# quadcopter.net
KiCad netlist of a schematic drawn in EAGLE
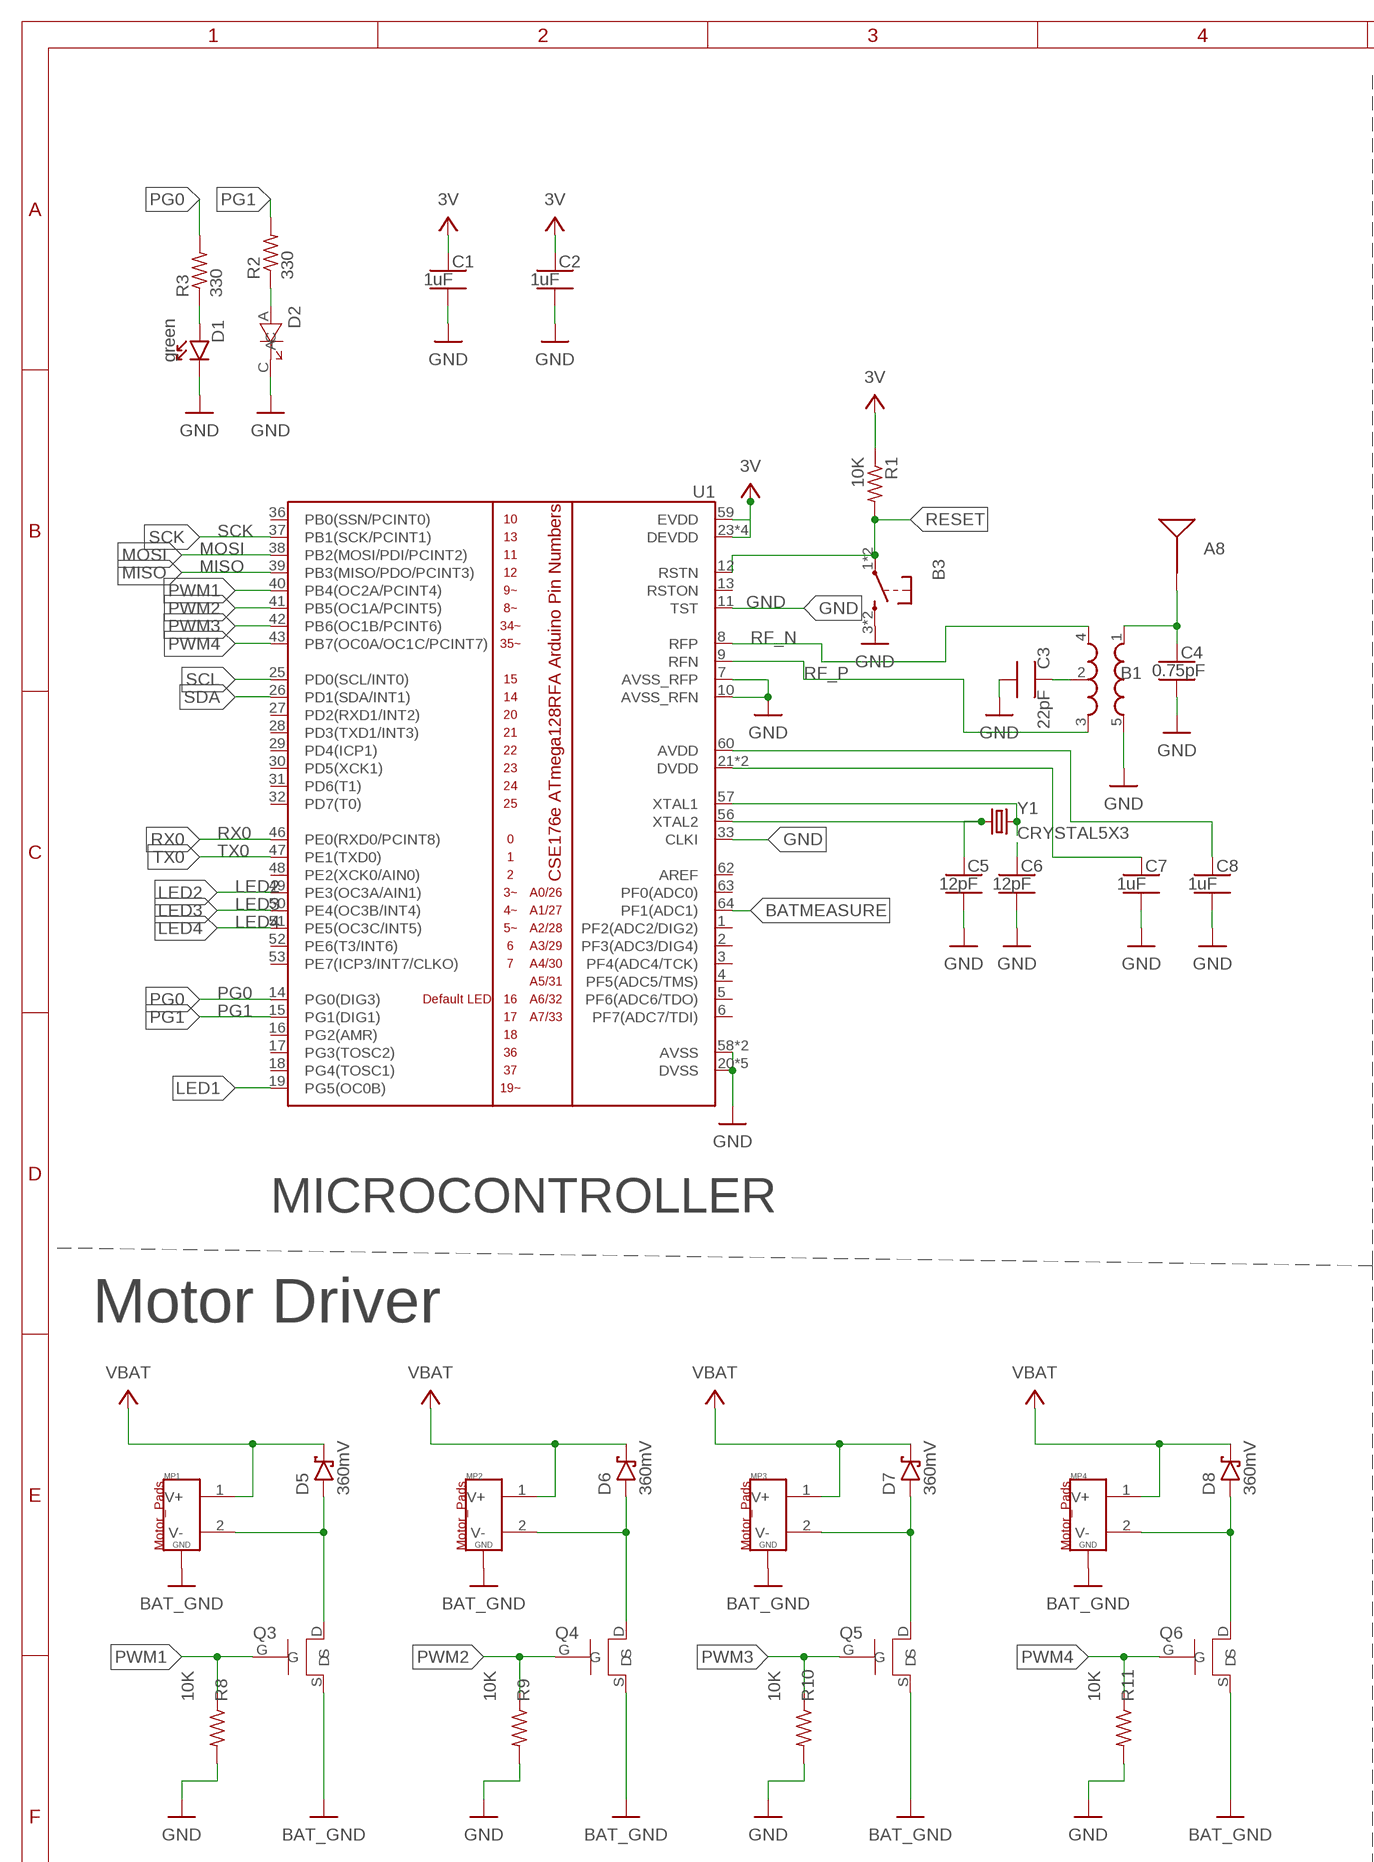
[diagram p0: schematic, sheet 1, part 1 of 2]
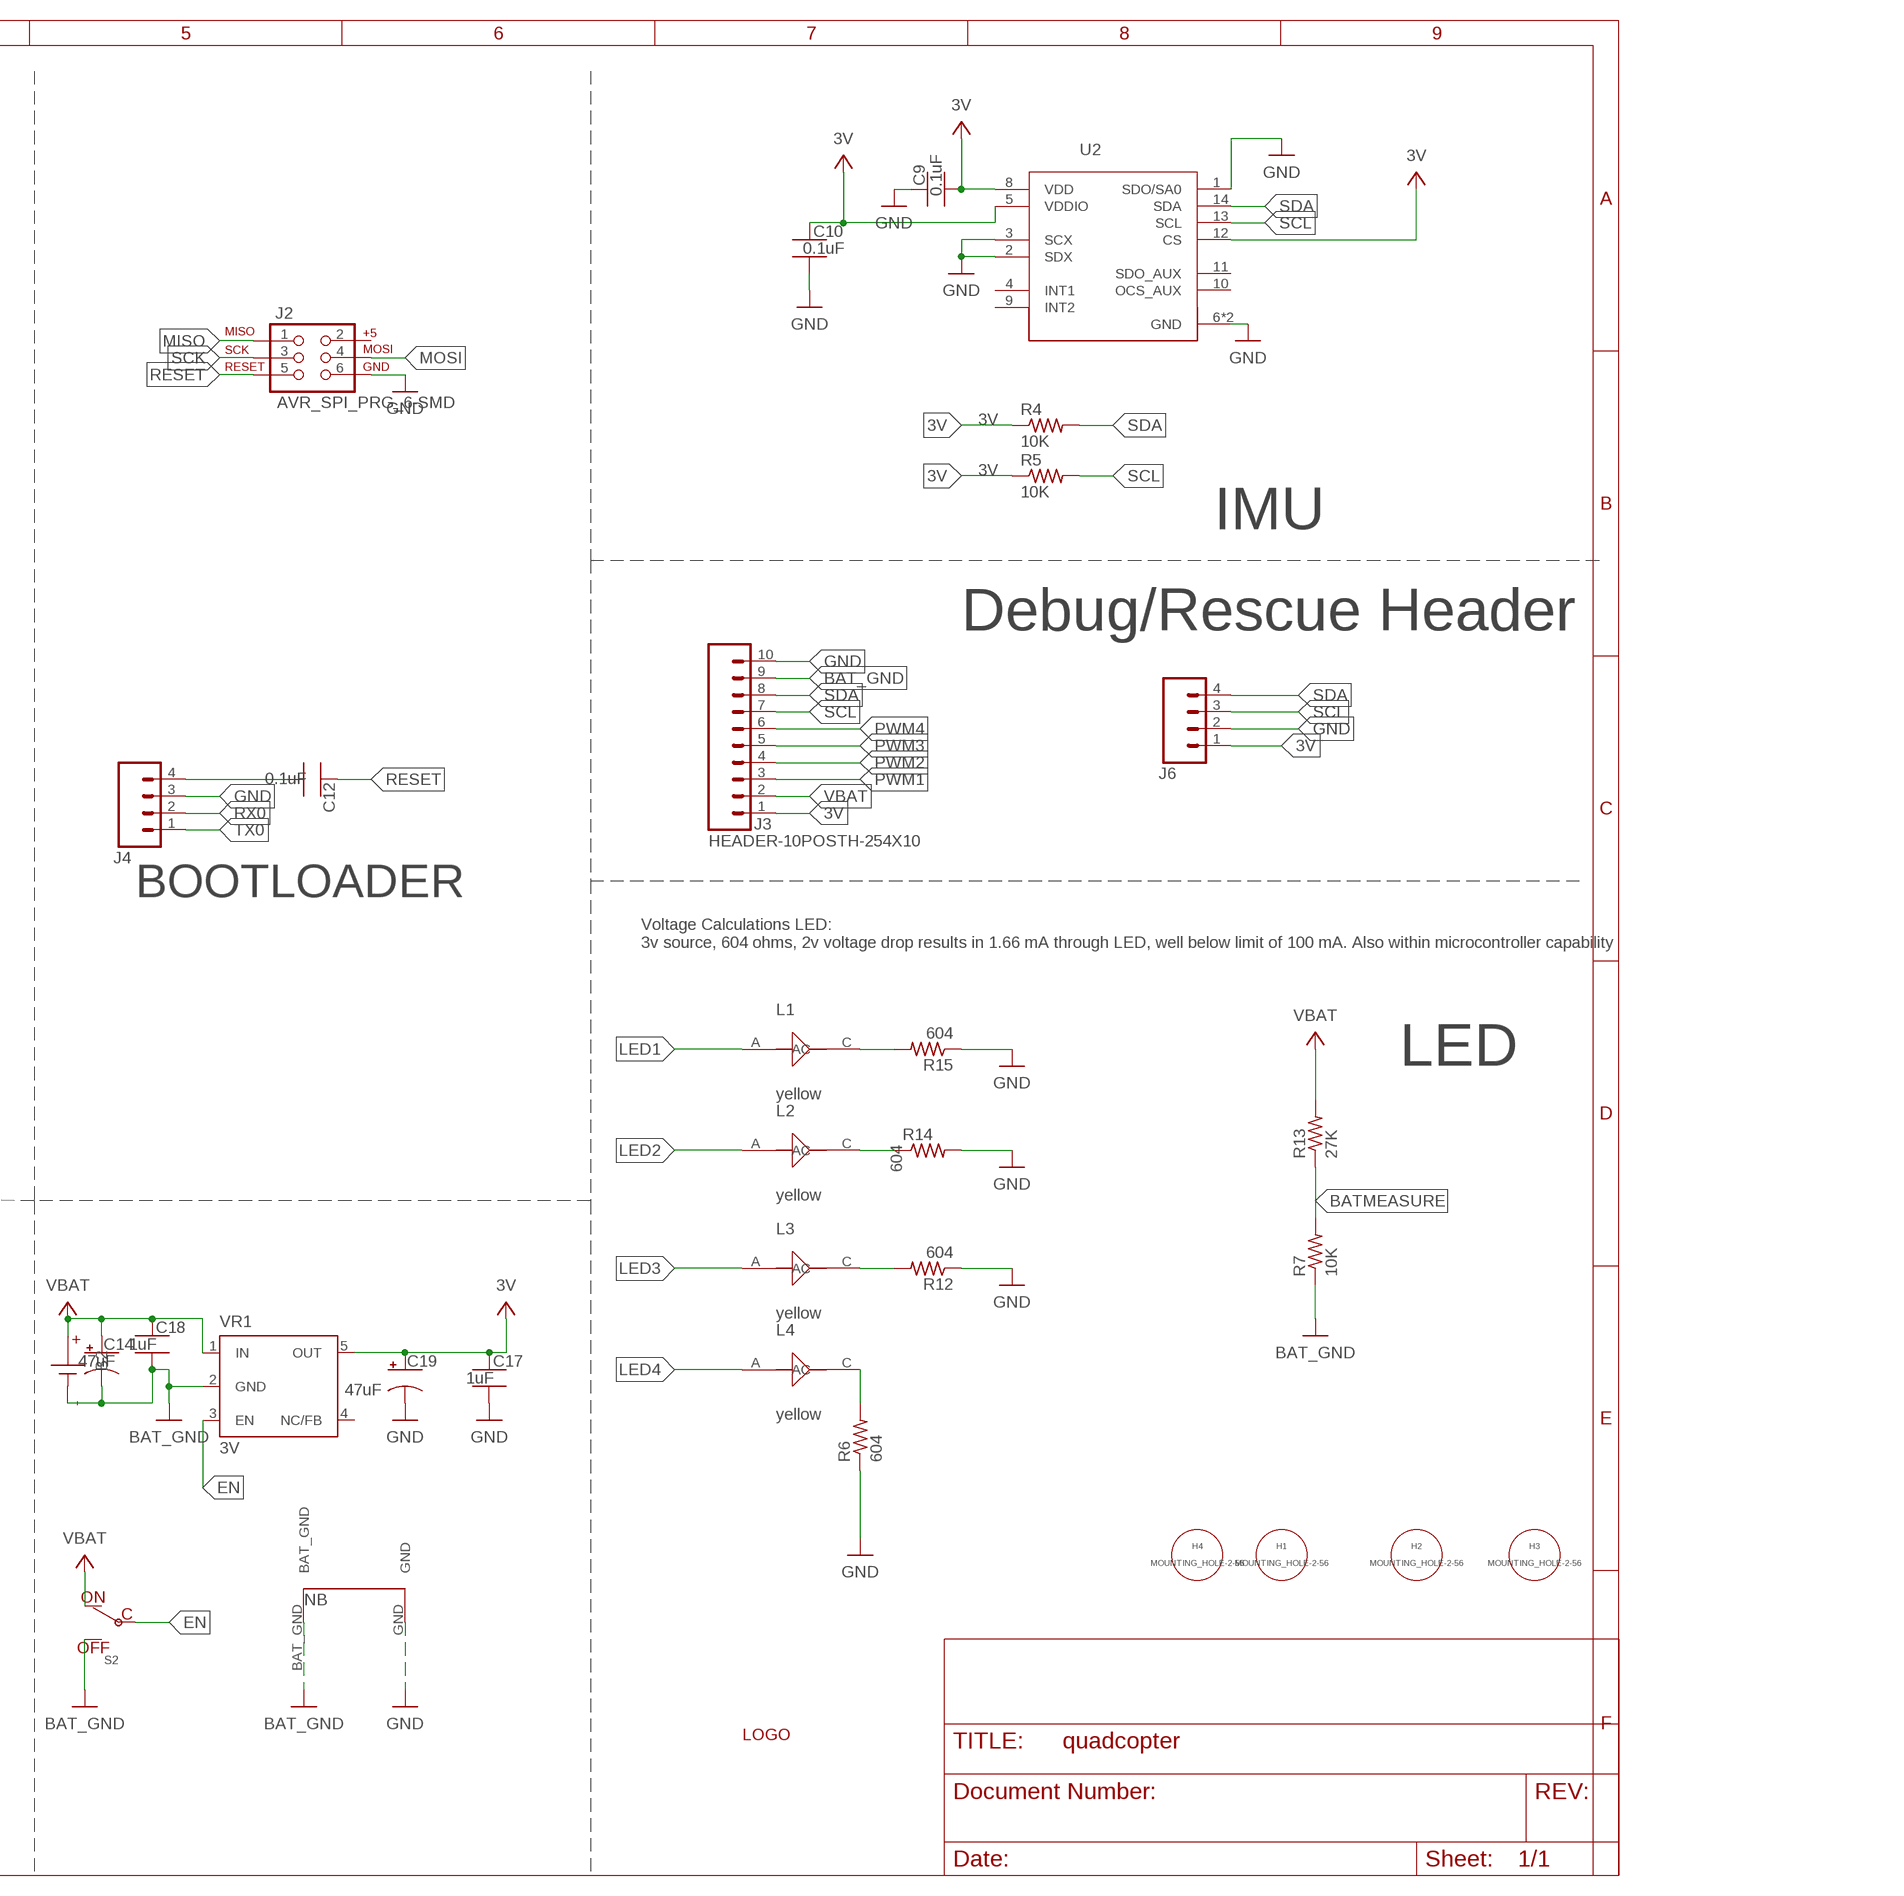
[diagram p1: schematic, sheet 1, part 2 of 2]

(export (version "E")
  (design (tool "Eeschema 10.0.6"))
  (components
    (comp (ref "A8")
      (value "ANTENNA-BOARD")
      (footprint "eagle-import:ANT_PCB_2.4GHZ_NRF8001_1.6MM_1OZ")
      (fields (field (name "MFR") "NA") (field (name "CREATOR") "Swanson"))
      (libsource (lib "eagle-import") (part "ANTENNA-BOARD"))
    )
    (comp (ref "B1")
      (value "BALUN0805")
      (footprint "eagle-import:BALUN")
      (fields
        (field (name "MFR") "Wurth Electronics Inc.")
        (field (name "MPN") "748421245")
        (field (name "CREATOR") "Swanson")
        (field (name "REVIEWER") "Swanson")
      )
      (libsource (lib "eagle-import") (part "BALUN0805"))
    )
    (comp (ref "B2")
      (value "BATTERY-SCREW-TERMINAL")
      (footprint "eagle-import:SCREW-TERMINAL-1X2-2.54MM")
      (fields (field (name "CREATOR") "Swanson"))
      (libsource (lib "eagle-import") (part "BATTERY-SCREW-TERMINAL"))
    )
    (comp (ref "B3")
      (value "PUSHBUTTON_SMD-VERTICAL-1")
      (footprint "eagle-import:TE_FSM8JSMA_HS")
      (fields
        (field (name "MFR") "TE Connectivity Alcoswitch Switches")
        (field (name "MPN") "FSM4JSMA")
        (field (name "CREATOR") "Swanson")
        (field (name "REVIEWER") "Swanson")
      )
      (libsource (lib "eagle-import") (part "PUSHBUTTON_SMD-VERTICAL-1"))
    )
    (comp (ref "C1")
      (value "1uF")
      (footprint "eagle-import:CAPC2012X140_HS")
      (fields
        (field (name "MFR") "Taiyo Yuden")
        (field (name "MPN") "TMK212B7105KG-T")
        (field (name "CREATOR") "Swanson")
        (field (name "REVIEWER") "Swanson")
      )
      (libsource (lib "eagle-import") (part "CAPACITOR-NP_SMD-2012-0805_CERAMIC-1UF"))
    )
    (comp (ref "C2")
      (value "1uF")
      (footprint "eagle-import:CAPC2012X140_HS")
      (fields
        (field (name "MFR") "Taiyo Yuden")
        (field (name "MPN") "TMK212B7105KG-T")
        (field (name "CREATOR") "Swanson")
        (field (name "REVIEWER") "Swanson")
      )
      (libsource (lib "eagle-import") (part "CAPACITOR-NP_SMD-2012-0805_CERAMIC-1UF"))
    )
    (comp (ref "C3")
      (value "22pF")
      (footprint "eagle-import:CAPC2012X140_HS")
      (fields
        (field (name "MFR") "Murata Electronics")
        (field (name "MPN") "GRM21A5C2E220JW01D")
        (field (name "CREATOR") "Swanson")
        (field (name "REVIEWER") "Swanson")
      )
      (libsource (lib "eagle-import") (part "CAPACITOR-NP_SMD-2012-0805_CERAMIC-22PF"))
    )
    (comp (ref "C4")
      (value "0.75pF")
      (footprint "eagle-import:CAPC2012X140_HS")
      (fields
        (field (name "MFR") "Murata Electronics")
        (field (name "MPN") "GQM2195C2AR75CB01D")
        (field (name "CREATOR") "Swanson")
        (field (name "REVIEWER") "Swanson")
      )
      (libsource (lib "eagle-import") (part "CAPACITOR-NP_SMD-2012-0805_CERAMIC-0.75PF"))
    )
    (comp (ref "C5")
      (value "12pF")
      (footprint "eagle-import:CAPC2012X140_HS")
      (fields
        (field (name "MFR") "Murata Electronics")
        (field (name "MPN") "GRM21A5C2E120JW01D")
        (field (name "CREATOR") "Swanson")
        (field (name "REVIEWER") "Swanson")
      )
      (libsource (lib "eagle-import") (part "CAPACITOR-NP_SMD-2012-0805_CERAMIC-12PF"))
    )
    (comp (ref "C6")
      (value "12pF")
      (footprint "eagle-import:CAPC2012X140_HS")
      (fields
        (field (name "MFR") "Murata Electronics")
        (field (name "MPN") "GRM21A5C2E120JW01D")
        (field (name "CREATOR") "Swanson")
        (field (name "REVIEWER") "Swanson")
      )
      (libsource (lib "eagle-import") (part "CAPACITOR-NP_SMD-2012-0805_CERAMIC-12PF"))
    )
    (comp (ref "C7")
      (value "1uF")
      (footprint "eagle-import:CAPC2012X140_HS")
      (fields
        (field (name "MFR") "Taiyo Yuden")
        (field (name "MPN") "TMK212B7105KG-T")
        (field (name "CREATOR") "Swanson")
        (field (name "REVIEWER") "Swanson")
      )
      (libsource (lib "eagle-import") (part "CAPACITOR-NP_SMD-2012-0805_CERAMIC-1UF"))
    )
    (comp (ref "C8")
      (value "1uF")
      (footprint "eagle-import:CAPC2012X140_HS")
      (fields
        (field (name "MFR") "Taiyo Yuden")
        (field (name "MPN") "TMK212B7105KG-T")
        (field (name "CREATOR") "Swanson")
        (field (name "REVIEWER") "Swanson")
      )
      (libsource (lib "eagle-import") (part "CAPACITOR-NP_SMD-2012-0805_CERAMIC-1UF"))
    )
    (comp (ref "C9")
      (value "0.1uF")
      (footprint "eagle-import:CAPC2012X140_HS")
      (fields
        (field (name "MFR") "TDK Corporation")
        (field (name "MPN") "C2012X7R2A104K125AA")
        (field (name "CREATOR") "Swanson")
        (field (name "REVIEWER") "Swanson")
      )
      (libsource (lib "eagle-import") (part "CAPACITOR-NP_SMD-2012-0805_CERAMIC-0.1UF"))
    )
    (comp (ref "C10")
      (value "0.1uF")
      (footprint "eagle-import:CAPC2012X140_HS")
      (fields
        (field (name "MFR") "TDK Corporation")
        (field (name "MPN") "C2012X7R2A104K125AA")
        (field (name "CREATOR") "Swanson")
        (field (name "REVIEWER") "Swanson")
      )
      (libsource (lib "eagle-import") (part "CAPACITOR-NP_SMD-2012-0805_CERAMIC-0.1UF"))
    )
    (comp (ref "C12")
      (value "0.1uF")
      (footprint "eagle-import:CAPC2012X140_HS")
      (fields
        (field (name "MFR") "TDK Corporation")
        (field (name "MPN") "C2012X7R2A104K125AA")
        (field (name "CREATOR") "Swanson")
        (field (name "REVIEWER") "Swanson")
      )
      (libsource (lib "eagle-import") (part "CAPACITOR-NP_SMD-2012-0805_CERAMIC-0.1UF"))
    )
    (comp (ref "C14")
      (value "47uF")
      (footprint "eagle-import:CAPMP3216X180")
      (fields
        (field (name "MFR") "AVX Corporation")
        (field (name "MPN") "TAJA476K006SNJV")
        (field (name "CREATOR") "Swanson")
      )
      (libsource (lib "eagle-import") (part "CAPACITOR-POL_47UF-SMD-1206-TAJA"))
    )
    (comp (ref "C17")
      (value "1uF")
      (footprint "eagle-import:CAPC2012X140_HS")
      (fields
        (field (name "MFR") "Taiyo Yuden")
        (field (name "MPN") "TMK212B7105KG-T")
        (field (name "CREATOR") "Swanson")
        (field (name "REVIEWER") "Swanson")
      )
      (libsource (lib "eagle-import") (part "CAPACITOR-NP_SMD-2012-0805_CERAMIC-1UF"))
    )
    (comp (ref "C18")
      (value "1uF")
      (footprint "eagle-import:CAPC2012X140_HS")
      (fields
        (field (name "MFR") "Taiyo Yuden")
        (field (name "MPN") "TMK212B7105KG-T")
        (field (name "CREATOR") "Swanson")
        (field (name "REVIEWER") "Swanson")
      )
      (libsource (lib "eagle-import") (part "CAPACITOR-NP_SMD-2012-0805_CERAMIC-1UF"))
    )
    (comp (ref "C19")
      (value "47uF")
      (footprint "eagle-import:CAPMP3216X180")
      (fields
        (field (name "MFR") "AVX Corporation")
        (field (name "MPN") "TAJA476K006SNJV")
        (field (name "CREATOR") "Swanson")
      )
      (libsource (lib "eagle-import") (part "CAPACITOR-POL_47UF-SMD-1206-TAJA"))
    )
    (comp (ref "D1")
      (value "green")
      (footprint "eagle-import:LEDSC125X200X120-2_HS")
      (fields
        (field (name "MFR") "Lite-On Inc")
        (field (name "MPN") "LTST-C170GKT")
        (field (name "CREATOR") "Swanson")
        (field (name "REVIEWER") "Swanson")
      )
      (libsource (lib "eagle-import") (part "DIODE-LED_SMD-2012-0805-GREEN"))
    )
    (comp (ref "D2")
      (value "LED-RED-160-1178-1-ND")
      (footprint "eagle-import:LED_160-1178-1-ND")
      (fields (field (name "CREATOR") "KaustubhKanagalekar"))
      (libsource (lib "eagle-import") (part "LED-RED-160-1178-1-ND"))
    )
    (comp (ref "D5")
      (value "360mV")
      (footprint "eagle-import:SODFL3516X96")
      (fields
        (field (name "MFR") "Toshiba Semiconductor and Storage")
        (field (name "MPN") "CRS08(TE85L,Q,M)")
        (field (name "CREATOR") "Swanson")
        (field (name "REVIEWER") "Swanson")
      )
      (libsource (lib "eagle-import") (part "DIODE-SCHOTTKY_-SMD-SOD123"))
    )
    (comp (ref "D6")
      (value "360mV")
      (footprint "eagle-import:SODFL3516X96")
      (fields
        (field (name "MFR") "Toshiba Semiconductor and Storage")
        (field (name "MPN") "CRS08(TE85L,Q,M)")
        (field (name "CREATOR") "Swanson")
        (field (name "REVIEWER") "Swanson")
      )
      (libsource (lib "eagle-import") (part "DIODE-SCHOTTKY_-SMD-SOD123"))
    )
    (comp (ref "D7")
      (value "360mV")
      (footprint "eagle-import:SODFL3516X96")
      (fields
        (field (name "MFR") "Toshiba Semiconductor and Storage")
        (field (name "MPN") "CRS08(TE85L,Q,M)")
        (field (name "CREATOR") "Swanson")
        (field (name "REVIEWER") "Swanson")
      )
      (libsource (lib "eagle-import") (part "DIODE-SCHOTTKY_-SMD-SOD123"))
    )
    (comp (ref "D8")
      (value "360mV")
      (footprint "eagle-import:SODFL3516X96")
      (fields
        (field (name "MFR") "Toshiba Semiconductor and Storage")
        (field (name "MPN") "CRS08(TE85L,Q,M)")
        (field (name "CREATOR") "Swanson")
        (field (name "REVIEWER") "Swanson")
      )
      (libsource (lib "eagle-import") (part "DIODE-SCHOTTKY_-SMD-SOD123"))
    )
    (comp (ref "H1")
      (value "MOUNTING_HOLE-2-56")
      (footprint "eagle-import:2-56-MOUNTING-HOLE-NO-METAL")
      (libsource (lib "eagle-import") (part "MOUNTING_HOLE-2-56"))
    )
    (comp (ref "H2")
      (value "MOUNTING_HOLE-2-56")
      (footprint "eagle-import:2-56-MOUNTING-HOLE-NO-METAL")
      (libsource (lib "eagle-import") (part "MOUNTING_HOLE-2-56"))
    )
    (comp (ref "H3")
      (value "MOUNTING_HOLE-2-56")
      (footprint "eagle-import:2-56-MOUNTING-HOLE-NO-METAL")
      (libsource (lib "eagle-import") (part "MOUNTING_HOLE-2-56"))
    )
    (comp (ref "H4")
      (value "MOUNTING_HOLE-2-56")
      (footprint "eagle-import:2-56-MOUNTING-HOLE-NO-METAL")
      (libsource (lib "eagle-import") (part "MOUNTING_HOLE-2-56"))
    )
    (comp (ref "J2")
      (value "AVR_SPI_PRG_6-SMD")
      (footprint "eagle-import:2X3-SMD")
      (fields
        (field (name "MFR") "Amphenol ICC (FCI)")
        (field (name "MPN") "95278-101A06LF")
        (field (name "CREATOR") "Swanson")
      )
      (libsource (lib "eagle-import") (part "AVR_SPI_PRG_6-SMD"))
    )
    (comp (ref "J3")
      (value "HEADER-10POSTH-254X10")
      (footprint "eagle-import:HDRV10W63P254_10X1_2540X254H838_HS")
      (fields
        (field (name "MFR") "Amphenol FCI")
        (field (name "MPN") "68000-110HLF")
        (field (name "CREATOR") "Swanson")
        (field (name "REVIEWER") "Swanson")
      )
      (libsource (lib "eagle-import") (part "HEADER-10POSTH-254X10"))
    )
    (comp (ref "J4")
      (value "HEADER-4POS-0.1IN-FEMALE-SMD-BOTTOM-ENTRY")
      (footprint "eagle-import:HEADER-1X4-BOTTOM-ENTRY")
      (fields
        (field (name "MFR") "TE Connectivity AMP Connectors")
        (field (name "MPN") "1241152-4")
        (field (name "CREATOR") "Swanson")
      )
      (libsource (lib "eagle-import") (part "HEADER-4POS-0.1IN-FEMALE-SMD-BOTTOM-ENTRY"))
    )
    (comp (ref "J6")
      (value "HEADER-4POS-0.1IN-FEMALE")
      (footprint "eagle-import:HDRVR4W80P254_1X4_1066X254X850B")
      (fields (field (name "CREATOR") "Swanson"))
      (libsource (lib "eagle-import") (part "HEADER-4POS-0.1IN-FEMALE"))
    )
    (comp (ref "L1")
      (value "yellow")
      (footprint "eagle-import:LEDC1507X80NYELLOW")
      (fields (field (name "CREATOR") "AlexanderHaken"))
      (libsource (lib "eagle-import") (part "LED_YELLOW"))
    )
    (comp (ref "L2")
      (value "yellow")
      (footprint "eagle-import:LEDC1507X80NYELLOW")
      (fields (field (name "CREATOR") "AlexanderHaken"))
      (libsource (lib "eagle-import") (part "LED_YELLOW"))
    )
    (comp (ref "L3")
      (value "yellow")
      (footprint "eagle-import:LEDC1507X80NYELLOW")
      (fields (field (name "CREATOR") "AlexanderHaken"))
      (libsource (lib "eagle-import") (part "LED_YELLOW"))
    )
    (comp (ref "L4")
      (value "yellow")
      (footprint "eagle-import:LEDC1507X80NYELLOW")
      (fields (field (name "CREATOR") "AlexanderHaken"))
      (libsource (lib "eagle-import") (part "LED_YELLOW"))
    )
    (comp (ref "LOGO")
      (value "PIDLOGO")
      (footprint "eagle-import:PIDLOGO")
      (libsource (lib "eagle-import") (part "PIDLOGO"))
    )
    (comp (ref "MP1")
      (value "MOTOR_PADS_GND-MOLEX-SMD")
      (footprint "eagle-import:MOLEX-0532610271")
      (fields
        (field (name "MFR") "Molex")
        (field (name "MPN") "532610271")
        (field (name "CREATOR") "Swanson")
      )
      (libsource (lib "eagle-import") (part "MOTOR_PADS_GND-MOLEX-SMD"))
    )
    (comp (ref "MP2")
      (value "MOTOR_PADS_GND-MOLEX-SMD")
      (footprint "eagle-import:MOLEX-0532610271")
      (fields
        (field (name "MFR") "Molex")
        (field (name "MPN") "532610271")
        (field (name "CREATOR") "Swanson")
      )
      (libsource (lib "eagle-import") (part "MOTOR_PADS_GND-MOLEX-SMD"))
    )
    (comp (ref "MP3")
      (value "MOTOR_PADS_GND-MOLEX-SMD")
      (footprint "eagle-import:MOLEX-0532610271")
      (fields
        (field (name "MFR") "Molex")
        (field (name "MPN") "532610271")
        (field (name "CREATOR") "Swanson")
      )
      (libsource (lib "eagle-import") (part "MOTOR_PADS_GND-MOLEX-SMD"))
    )
    (comp (ref "MP4")
      (value "MOTOR_PADS_GND-MOLEX-SMD")
      (footprint "eagle-import:MOLEX-0532610271")
      (fields
        (field (name "MFR") "Molex")
        (field (name "MPN") "532610271")
        (field (name "CREATOR") "Swanson")
      )
      (libsource (lib "eagle-import") (part "MOTOR_PADS_GND-MOLEX-SMD"))
    )
    (comp (ref "NB")
      (value "NETBRIDGE")
      (footprint "eagle-import:NETBRIDGE")
      (libsource (lib "eagle-import") (part "NETBRIDGE"))
    )
    (comp (ref "Q3")
      (value "MOSFET-FET-SI2302CDS-T1-E3CT-NDSI2302CDS-T1-E3CT-ND")
      (footprint "eagle-import:MOSFET_FET_SI2302CDS-T1-E3CT-ND")
      (fields (field (name "CREATOR") "KaustubhKanagalekar"))
      (libsource (lib "eagle-import") (part "MOSFET-FET-SI2302CDS-T1-E3CT-NDSI2302CDS-T1-E3CT-ND"))
    )
    (comp (ref "Q4")
      (value "MOSFET-FET-SI2302CDS-T1-E3CT-NDSI2302CDS-T1-E3CT-ND")
      (footprint "eagle-import:MOSFET_FET_SI2302CDS-T1-E3CT-ND")
      (fields (field (name "CREATOR") "KaustubhKanagalekar"))
      (libsource (lib "eagle-import") (part "MOSFET-FET-SI2302CDS-T1-E3CT-NDSI2302CDS-T1-E3CT-ND"))
    )
    (comp (ref "Q5")
      (value "MOSFET-FET-SI2302CDS-T1-E3CT-NDSI2302CDS-T1-E3CT-ND")
      (footprint "eagle-import:MOSFET_FET_SI2302CDS-T1-E3CT-ND")
      (fields (field (name "CREATOR") "KaustubhKanagalekar"))
      (libsource (lib "eagle-import") (part "MOSFET-FET-SI2302CDS-T1-E3CT-NDSI2302CDS-T1-E3CT-ND"))
    )
    (comp (ref "Q6")
      (value "MOSFET-FET-SI2302CDS-T1-E3CT-NDSI2302CDS-T1-E3CT-ND")
      (footprint "eagle-import:MOSFET_FET_SI2302CDS-T1-E3CT-ND")
      (fields (field (name "CREATOR") "KaustubhKanagalekar"))
      (libsource (lib "eagle-import") (part "MOSFET-FET-SI2302CDS-T1-E3CT-NDSI2302CDS-T1-E3CT-ND"))
    )
    (comp (ref "R1")
      (value "10K")
      (footprint "eagle-import:RESC2012X60_HS")
      (fields
        (field (name "MFR") "Yageo")
        (field (name "MPN") "RC0805JR-0710KL")
        (field (name "CREATOR") "Swanson")
        (field (name "REVIEWER") "Swanson")
      )
      (libsource (lib "eagle-import") (part "RESISTOR_SMD-2012-0805-10K"))
    )
    (comp (ref "R2")
      (value "330")
      (footprint "eagle-import:RESC2012X60_HS")
      (fields
        (field (name "MFR") "Yageo")
        (field (name "MPN") "RC0805JR-07330RL")
        (field (name "CREATOR") "Swanson")
        (field (name "REVIEWER") "Swanson")
      )
      (libsource (lib "eagle-import") (part "RESISTOR_SMD-2012-0805-330"))
    )
    (comp (ref "R3")
      (value "330")
      (footprint "eagle-import:RESC2012X60_HS")
      (fields
        (field (name "MFR") "Yageo")
        (field (name "MPN") "RC0805JR-07330RL")
        (field (name "CREATOR") "Swanson")
        (field (name "REVIEWER") "Swanson")
      )
      (libsource (lib "eagle-import") (part "RESISTOR_SMD-2012-0805-330"))
    )
    (comp (ref "R4")
      (value "10K")
      (footprint "eagle-import:RESC2012X60_HS")
      (fields
        (field (name "MFR") "Yageo")
        (field (name "MPN") "RC0805JR-0710KL")
        (field (name "CREATOR") "Swanson")
        (field (name "REVIEWER") "Swanson")
      )
      (libsource (lib "eagle-import") (part "RESISTOR_SMD-2012-0805-10K"))
    )
    (comp (ref "R5")
      (value "10K")
      (footprint "eagle-import:RESC2012X60_HS")
      (fields
        (field (name "MFR") "Yageo")
        (field (name "MPN") "RC0805JR-0710KL")
        (field (name "CREATOR") "Swanson")
        (field (name "REVIEWER") "Swanson")
      )
      (libsource (lib "eagle-import") (part "RESISTOR_SMD-2012-0805-10K"))
    )
    (comp (ref "R6")
      (value "604")
      (footprint "eagle-import:RESC2012X60_HS")
      (fields (field (name "CREATOR") "Swanson"))
      (libsource (lib "eagle-import") (part "RESISTOR_SMD-2012-0805-604"))
    )
    (comp (ref "R7")
      (value "10K")
      (footprint "eagle-import:RESC2012X60_HS")
      (fields
        (field (name "MFR") "Yageo")
        (field (name "MPN") "RC0805JR-0710KL")
        (field (name "CREATOR") "Swanson")
        (field (name "REVIEWER") "Swanson")
      )
      (libsource (lib "eagle-import") (part "RESISTOR_SMD-2012-0805-10K"))
    )
    (comp (ref "R8")
      (value "10K")
      (footprint "eagle-import:RESC2012X60_HS")
      (fields
        (field (name "MFR") "Yageo")
        (field (name "MPN") "RC0805JR-0710KL")
        (field (name "CREATOR") "Swanson")
        (field (name "REVIEWER") "Swanson")
      )
      (libsource (lib "eagle-import") (part "RESISTOR_SMD-2012-0805-10K"))
    )
    (comp (ref "R9")
      (value "10K")
      (footprint "eagle-import:RESC2012X60_HS")
      (fields
        (field (name "MFR") "Yageo")
        (field (name "MPN") "RC0805JR-0710KL")
        (field (name "CREATOR") "Swanson")
        (field (name "REVIEWER") "Swanson")
      )
      (libsource (lib "eagle-import") (part "RESISTOR_SMD-2012-0805-10K"))
    )
    (comp (ref "R10")
      (value "10K")
      (footprint "eagle-import:RESC2012X60_HS")
      (fields
        (field (name "MFR") "Yageo")
        (field (name "MPN") "RC0805JR-0710KL")
        (field (name "CREATOR") "Swanson")
        (field (name "REVIEWER") "Swanson")
      )
      (libsource (lib "eagle-import") (part "RESISTOR_SMD-2012-0805-10K"))
    )
    (comp (ref "R11")
      (value "10K")
      (footprint "eagle-import:RESC2012X60_HS")
      (fields
        (field (name "MFR") "Yageo")
        (field (name "MPN") "RC0805JR-0710KL")
        (field (name "CREATOR") "Swanson")
        (field (name "REVIEWER") "Swanson")
      )
      (libsource (lib "eagle-import") (part "RESISTOR_SMD-2012-0805-10K"))
    )
    (comp (ref "R12")
      (value "604")
      (footprint "eagle-import:RESC2012X60_HS")
      (fields (field (name "CREATOR") "Swanson"))
      (libsource (lib "eagle-import") (part "RESISTOR_SMD-2012-0805-604"))
    )
    (comp (ref "R13")
      (value "27K")
      (footprint "eagle-import:RESC2012X60_HS")
      (fields (field (name "CREATOR") "Swanson"))
      (libsource (lib "eagle-import") (part "RESISTOR_SMD-2012-0805-27K"))
    )
    (comp (ref "R14")
      (value "604")
      (footprint "eagle-import:RESC2012X60_HS")
      (fields (field (name "CREATOR") "Swanson"))
      (libsource (lib "eagle-import") (part "RESISTOR_SMD-2012-0805-604"))
    )
    (comp (ref "R15")
      (value "604")
      (footprint "eagle-import:RESC2012X60_HS")
      (fields (field (name "CREATOR") "Swanson"))
      (libsource (lib "eagle-import") (part "RESISTOR_SMD-2012-0805-604"))
    )
    (comp (ref "S2")
      (value "POWER-SWITCH-MFS201N-9-Z-SMD-EDGE")
      (footprint "eagle-import:JS102011SAQN")
      (fields
        (field (name "MFR") "C&K")
        (field (name "MPN") "JS102011SAQN")
        (field (name "CREATOR") "Swanson")
      )
      (libsource (lib "eagle-import") (part "POWER-SWITCH-MFS201N-9-Z-SMD-EDGE"))
    )
    (comp (ref "U1")
      (value "ATMEGA128RFA1")
      (footprint "eagle-import:QFN-64")
      (fields
        (field (name "MFR") "Microchip Technology")
        (field (name "MPN") "ATMEGA128RFA1-ZU")
        (field (name "CREATOR") "Swanson")
        (field (name "REVIEWER") "Swanson")
      )
      (libsource (lib "eagle-import") (part "ATMEGA128RFA1"))
    )
    (comp (ref "U2")
      (value "IMU-LSM6DSOXTR-497-18367-1-ND497-18367-1-ND")
      (footprint "eagle-import:LSM6DS0")
      (fields (field (name "CREATOR") "KaustubhKanagalekar"))
      (libsource (lib "eagle-import") (part "IMU-LSM6DSOXTR-497-18367-1-ND497-18367-1-ND"))
    )
    (comp (ref "VR1")
      (value "3V")
      (footprint "eagle-import:SOT23-DBV")
      (fields
        (field (name "MFR") "Texas Instruments")
        (field (name "MPN") "LP3985IM5X-3.0/NOPB")
        (field (name "CREATOR") "Swanson")
        (field (name "REVIEWER") "Swanson")
      )
      (libsource (lib "eagle-import") (part "TPS73633-DBVT3V"))
    )
    (comp (ref "Y1")
      (value "CRYSTAL5X3")
      (footprint "eagle-import:CRYSTAL-SMD-5X3")
      (fields
        (field (name "MFR") "Abracon LLC")
        (field (name "MPN") "ABM3B-16.000MHZ-B2-T")
        (field (name "CREATOR") "Swanson")
        (field (name "REVIEWER") "Swanson")
      )
      (libsource (lib "eagle-import") (part "CRYSTAL5X3"))
    )
  )
  (nets
    (net (code "1") (name "/RF_N") (class "Default")
      (node (ref "B1") (pin "4") (pinfunction "OUT1_4") (pintype "bidirectional"))
      (node (ref "U1") (pin "8") (pinfunction "RFP_8") (pintype "bidirectional"))
    )
    (net (code "2") (name "/RF_P") (class "Default")
      (node (ref "B1") (pin "3") (pinfunction "OUT2_3") (pintype "bidirectional"))
      (node (ref "U1") (pin "9") (pinfunction "RFN_9") (pintype "bidirectional"))
    )
    (net (code "3") (name "3V") (class "Default")
      (node (ref "C1") (pin "1") (pinfunction "1_1") (pintype "passive"))
      (node (ref "C10") (pin "1") (pinfunction "1_1") (pintype "passive"))
      (node (ref "C17") (pin "1") (pinfunction "1_1") (pintype "passive"))
      (node (ref "C19") (pin "1") (pinfunction "+_1") (pintype "passive"))
      (node (ref "C2") (pin "1") (pinfunction "1_1") (pintype "passive"))
      (node (ref "C9") (pin "2") (pinfunction "2_2") (pintype "passive"))
      (node (ref "J3") (pin "1") (pinfunction "1_1") (pintype "passive"))
      (node (ref "J6") (pin "1") (pinfunction "1_1") (pintype "bidirectional"))
      (node (ref "R1") (pin "1") (pinfunction "1_1") (pintype "passive"))
      (node (ref "R4") (pin "1") (pinfunction "1_1") (pintype "passive"))
      (node (ref "R5") (pin "1") (pinfunction "1_1") (pintype "passive"))
      (node (ref "U1") (pin "23") (pinfunction "DEVDD_23") (pintype "bidirectional"))
      (node (ref "U1") (pin "34") (pinfunction "DEVDD_34") (pintype "bidirectional"))
      (node (ref "U1") (pin "44") (pinfunction "DEVDD_44") (pintype "bidirectional"))
      (node (ref "U1") (pin "54") (pinfunction "DEVDD_54") (pintype "bidirectional"))
      (node (ref "U1") (pin "59") (pinfunction "EVDD_59") (pintype "bidirectional"))
      (node (ref "U2") (pin "12") (pinfunction "CS_12") (pintype "bidirectional"))
      (node (ref "U2") (pin "5") (pinfunction "VDDIO_5") (pintype "bidirectional"))
      (node (ref "U2") (pin "8") (pinfunction "VDD_8") (pintype "bidirectional"))
      (node (ref "VR1") (pin "5") (pinfunction "OUT_5") (pintype "passive"))
    )
    (net (code "4") (name "BATMEASURE") (class "Default")
      (node (ref "R13") (pin "1") (pinfunction "1_1") (pintype "passive"))
      (node (ref "R7") (pin "2") (pinfunction "2_2") (pintype "passive"))
      (node (ref "U1") (pin "64") (pinfunction "PF1(ADC1)_64") (pintype "bidirectional"))
    )
    (net (code "5") (name "BAT_GND") (class "Default")
      (node (ref "B2") (pin "1") (pinfunction "N_1") (pintype "bidirectional"))
      (node (ref "C14") (pin "2") (pinfunction "-_2") (pintype "passive"))
      (node (ref "C18") (pin "2") (pinfunction "2_2") (pintype "passive"))
      (node (ref "J3") (pin "9") (pinfunction "9_9") (pintype "passive"))
      (node (ref "MP1") (pin "G1") (pinfunction "GND_G1") (pintype "bidirectional"))
      (node (ref "MP1") (pin "G2") (pinfunction "GND_G2") (pintype "bidirectional"))
      (node (ref "MP2") (pin "G1") (pinfunction "GND_G1") (pintype "bidirectional"))
      (node (ref "MP2") (pin "G2") (pinfunction "GND_G2") (pintype "bidirectional"))
      (node (ref "MP3") (pin "G1") (pinfunction "GND_G1") (pintype "bidirectional"))
      (node (ref "MP3") (pin "G2") (pinfunction "GND_G2") (pintype "bidirectional"))
      (node (ref "MP4") (pin "G1") (pinfunction "GND_G1") (pintype "bidirectional"))
      (node (ref "MP4") (pin "G2") (pinfunction "GND_G2") (pintype "bidirectional"))
      (node (ref "NB") (pin "BAT_GND") (pinfunction "BAT_GND_BAT_GND") (pintype "bidirectional"))
      (node (ref "Q3") (pin "S") (pinfunction "S_S") (pintype "bidirectional"))
      (node (ref "Q4") (pin "S") (pinfunction "S_S") (pintype "bidirectional"))
      (node (ref "Q5") (pin "S") (pinfunction "S_S") (pintype "bidirectional"))
      (node (ref "Q6") (pin "S") (pinfunction "S_S") (pintype "bidirectional"))
      (node (ref "R7") (pin "1") (pinfunction "1_1") (pintype "passive"))
      (node (ref "S2") (pin "A") (pinfunction "OFF_A") (pintype "bidirectional"))
      (node (ref "VR1") (pin "2") (pinfunction "GND_2") (pintype "input"))
    )
    (net (code "6") (name "EN") (class "Default")
      (node (ref "S2") (pin "C") (pinfunction "C_C") (pintype "bidirectional"))
      (node (ref "VR1") (pin "3") (pinfunction "EN_3") (pintype "input"))
    )
    (net (code "7") (name "GND") (class "Default")
      (node (ref "B1") (pin "5") (pinfunction "GND_5") (pintype "bidirectional"))
      (node (ref "B3") (pin "3") (pinfunction "2_3") (pintype "passive"))
      (node (ref "B3") (pin "4") (pinfunction "2_4") (pintype "passive"))
      (node (ref "C1") (pin "2") (pinfunction "2_2") (pintype "passive"))
      (node (ref "C10") (pin "2") (pinfunction "2_2") (pintype "passive"))
      (node (ref "C17") (pin "2") (pinfunction "2_2") (pintype "passive"))
      (node (ref "C19") (pin "2") (pinfunction "-_2") (pintype "passive"))
      (node (ref "C2") (pin "2") (pinfunction "2_2") (pintype "passive"))
      (node (ref "C3") (pin "2") (pinfunction "2_2") (pintype "passive"))
      (node (ref "C4") (pin "2") (pinfunction "2_2") (pintype "passive"))
      (node (ref "C5") (pin "2") (pinfunction "2_2") (pintype "passive"))
      (node (ref "C6") (pin "2") (pinfunction "2_2") (pintype "passive"))
      (node (ref "C7") (pin "2") (pinfunction "2_2") (pintype "passive"))
      (node (ref "C8") (pin "2") (pinfunction "2_2") (pintype "passive"))
      (node (ref "C9") (pin "1") (pinfunction "1_1") (pintype "passive"))
      (node (ref "D1") (pin "C") (pinfunction "C_C") (pintype "passive"))
      (node (ref "D2") (pin "C") (pinfunction "C_C") (pintype "bidirectional"))
      (node (ref "J2") (pin "6") (pinfunction "6_6") (pintype "passive"))
      (node (ref "J3") (pin "10") (pinfunction "10_10") (pintype "passive"))
      (node (ref "J4") (pin "3") (pinfunction "3_3") (pintype "bidirectional"))
      (node (ref "J6") (pin "2") (pinfunction "2_2") (pintype "bidirectional"))
      (node (ref "NB") (pin "GND") (pinfunction "GND_GND") (pintype "bidirectional"))
      (node (ref "R10") (pin "2") (pinfunction "2_2") (pintype "passive"))
      (node (ref "R11") (pin "2") (pinfunction "2_2") (pintype "passive"))
      (node (ref "R12") (pin "1") (pinfunction "1_1") (pintype "passive"))
      (node (ref "R14") (pin "2") (pinfunction "2_2") (pintype "passive"))
      (node (ref "R15") (pin "1") (pinfunction "1_1") (pintype "passive"))
      (node (ref "R6") (pin "1") (pinfunction "1_1") (pintype "passive"))
      (node (ref "R8") (pin "2") (pinfunction "2_2") (pintype "passive"))
      (node (ref "R9") (pin "2") (pinfunction "2_2") (pintype "passive"))
      (node (ref "U1") (pin "10") (pinfunction "AVSS_RFN_10") (pintype "bidirectional"))
      (node (ref "U1") (pin "11") (pinfunction "TST_11") (pintype "bidirectional"))
      (node (ref "U1") (pin "20") (pinfunction "DVSS_20") (pintype "bidirectional"))
      (node (ref "U1") (pin "24") (pinfunction "DVSS_24") (pintype "bidirectional"))
      (node (ref "U1") (pin "33") (pinfunction "CLKI_33") (pintype "bidirectional"))
      (node (ref "U1") (pin "35") (pinfunction "DVSS_35") (pintype "bidirectional"))
      (node (ref "U1") (pin "45") (pinfunction "DVSS_45") (pintype "bidirectional"))
      (node (ref "U1") (pin "55") (pinfunction "DVSS_55") (pintype "bidirectional"))
      (node (ref "U1") (pin "58") (pinfunction "AVSS_58") (pintype "bidirectional"))
      (node (ref "U1") (pin "61") (pinfunction "AVSS_61") (pintype "bidirectional"))
      (node (ref "U1") (pin "7") (pinfunction "AVSS_RFP_7") (pintype "bidirectional"))
      (node (ref "U2") (pin "1") (pinfunction "SDO/SA0_1") (pintype "bidirectional"))
      (node (ref "U2") (pin "2") (pinfunction "SDX_2") (pintype "bidirectional"))
      (node (ref "U2") (pin "3") (pinfunction "SCX_3") (pintype "bidirectional"))
      (node (ref "U2") (pin "6") (pinfunction "GND_6") (pintype "bidirectional"))
      (node (ref "U2") (pin "7") (pinfunction "GND_7") (pintype "bidirectional"))
    )
    (net (code "8") (name "LED1") (class "Default")
      (node (ref "L1") (pin "A") (pinfunction "A_A") (pintype "bidirectional"))
      (node (ref "U1") (pin "19") (pinfunction "PG5(OC0B)_19") (pintype "bidirectional"))
    )
    (net (code "9") (name "LED2") (class "Default")
      (node (ref "L2") (pin "A") (pinfunction "A_A") (pintype "bidirectional"))
      (node (ref "U1") (pin "49") (pinfunction "PE3(OC3A/AIN1)_49") (pintype "bidirectional"))
    )
    (net (code "10") (name "LED3") (class "Default")
      (node (ref "L3") (pin "A") (pinfunction "A_A") (pintype "bidirectional"))
      (node (ref "U1") (pin "50") (pinfunction "PE4(OC3B/INT4)_50") (pintype "bidirectional"))
    )
    (net (code "11") (name "LED4") (class "Default")
      (node (ref "L4") (pin "A") (pinfunction "A_A") (pintype "bidirectional"))
      (node (ref "U1") (pin "51") (pinfunction "PE5(OC3C/INT5)_51") (pintype "bidirectional"))
    )
    (net (code "12") (name "MISO") (class "Default")
      (node (ref "J2") (pin "1") (pinfunction "1_1") (pintype "passive"))
      (node (ref "U1") (pin "39") (pinfunction "PB3(MISO/PDO/PCINT3)_39") (pintype "bidirectional"))
    )
    (net (code "13") (name "MOSI") (class "Default")
      (node (ref "J2") (pin "4") (pinfunction "4_4") (pintype "passive"))
      (node (ref "U1") (pin "38") (pinfunction "PB2(MOSI/PDI/PCINT2)_38") (pintype "bidirectional"))
    )
    (net (code "14") (name "Net-(A8-SIGNAL)") (class "Default")
      (node (ref "A8") (pin "FEED") (pinfunction "SIGNAL_FEED") (pintype "bidirectional"))
      (node (ref "B1") (pin "1") (pinfunction "IN_1") (pintype "bidirectional"))
      (node (ref "C4") (pin "1") (pinfunction "1_1") (pintype "passive"))
    )
    (net (code "15") (name "Net-(B1-GND-Pad2)") (class "Default")
      (node (ref "B1") (pin "2") (pinfunction "GND_2") (pintype "bidirectional"))
      (node (ref "C3") (pin "1") (pinfunction "1_1") (pintype "passive"))
    )
    (net (code "16") (name "Net-(C7-Pad1)") (class "Default")
      (node (ref "C7") (pin "1") (pinfunction "1_1") (pintype "passive"))
      (node (ref "U1") (pin "21") (pinfunction "DVDD_21") (pintype "bidirectional"))
      (node (ref "U1") (pin "22") (pinfunction "DVDD_22") (pintype "bidirectional"))
    )
    (net (code "17") (name "Net-(C12-Pad2)") (class "Default")
      (node (ref "C12") (pin "2") (pinfunction "2_2") (pintype "passive"))
      (node (ref "J4") (pin "4") (pinfunction "4_4") (pintype "bidirectional"))
    )
    (net (code "18") (name "Net-(D1-PadA)") (class "Default")
      (node (ref "D1") (pin "A") (pinfunction "A_A") (pintype "passive"))
      (node (ref "R3") (pin "1") (pinfunction "1_1") (pintype "passive"))
    )
    (net (code "19") (name "Net-(D2-PadA)") (class "Default")
      (node (ref "D2") (pin "A") (pinfunction "A_A") (pintype "bidirectional"))
      (node (ref "R2") (pin "1") (pinfunction "1_1") (pintype "passive"))
    )
    (net (code "20") (name "Net-(D5-A)") (class "Default")
      (node (ref "D5") (pin "2") (pinfunction "A_2") (pintype "passive"))
      (node (ref "MP1") (pin "2") (pinfunction "V-_2") (pintype "bidirectional"))
      (node (ref "Q3") (pin "D") (pinfunction "D_D") (pintype "bidirectional"))
    )
    (net (code "21") (name "Net-(D6-A)") (class "Default")
      (node (ref "D6") (pin "2") (pinfunction "A_2") (pintype "passive"))
      (node (ref "MP2") (pin "2") (pinfunction "V-_2") (pintype "bidirectional"))
      (node (ref "Q4") (pin "D") (pinfunction "D_D") (pintype "bidirectional"))
    )
    (net (code "22") (name "Net-(D7-A)") (class "Default")
      (node (ref "D7") (pin "2") (pinfunction "A_2") (pintype "passive"))
      (node (ref "MP3") (pin "2") (pinfunction "V-_2") (pintype "bidirectional"))
      (node (ref "Q5") (pin "D") (pinfunction "D_D") (pintype "bidirectional"))
    )
    (net (code "23") (name "Net-(D8-A)") (class "Default")
      (node (ref "D8") (pin "2") (pinfunction "A_2") (pintype "passive"))
      (node (ref "MP4") (pin "2") (pinfunction "V-_2") (pintype "bidirectional"))
      (node (ref "Q6") (pin "D") (pinfunction "D_D") (pintype "bidirectional"))
    )
    (net (code "24") (name "Net-(L1-PadC)") (class "Default")
      (node (ref "L1") (pin "C") (pinfunction "C_C") (pintype "bidirectional"))
      (node (ref "R15") (pin "2") (pinfunction "2_2") (pintype "passive"))
    )
    (net (code "25") (name "Net-(L2-PadC)") (class "Default")
      (node (ref "L2") (pin "C") (pinfunction "C_C") (pintype "bidirectional"))
      (node (ref "R14") (pin "1") (pinfunction "1_1") (pintype "passive"))
    )
    (net (code "26") (name "Net-(L3-PadC)") (class "Default")
      (node (ref "L3") (pin "C") (pinfunction "C_C") (pintype "bidirectional"))
      (node (ref "R12") (pin "2") (pinfunction "2_2") (pintype "passive"))
    )
    (net (code "27") (name "Net-(L4-PadC)") (class "Default")
      (node (ref "L4") (pin "C") (pinfunction "C_C") (pintype "bidirectional"))
      (node (ref "R6") (pin "2") (pinfunction "2_2") (pintype "passive"))
    )
    (net (code "28") (name "Net-(U1-AVDD)") (class "Default")
      (node (ref "C8") (pin "1") (pinfunction "1_1") (pintype "passive"))
      (node (ref "U1") (pin "60") (pinfunction "AVDD_60") (pintype "bidirectional"))
    )
    (net (code "29") (name "Net-(U1-XTAL1)") (class "Default")
      (node (ref "C6") (pin "1") (pinfunction "1_1") (pintype "passive"))
      (node (ref "U1") (pin "57") (pinfunction "XTAL1_57") (pintype "bidirectional"))
      (node (ref "Y1") (pin "3") (pinfunction "2_3") (pintype "passive"))
    )
    (net (code "30") (name "Net-(U1-XTAL2)") (class "Default")
      (node (ref "C5") (pin "1") (pinfunction "1_1") (pintype "passive"))
      (node (ref "U1") (pin "56") (pinfunction "XTAL2_56") (pintype "bidirectional"))
      (node (ref "Y1") (pin "1") (pinfunction "1_1") (pintype "passive"))
    )
    (net (code "31") (name "PG0") (class "Default")
      (node (ref "R3") (pin "2") (pinfunction "2_2") (pintype "passive"))
      (node (ref "U1") (pin "14") (pinfunction "PG0(DIG3)_14") (pintype "bidirectional"))
    )
    (net (code "32") (name "PG1") (class "Default")
      (node (ref "R2") (pin "2") (pinfunction "2_2") (pintype "passive"))
      (node (ref "U1") (pin "15") (pinfunction "PG1(DIG1)_15") (pintype "bidirectional"))
    )
    (net (code "33") (name "PWM1") (class "Default")
      (node (ref "J3") (pin "3") (pinfunction "3_3") (pintype "passive"))
      (node (ref "Q3") (pin "G") (pinfunction "G_G") (pintype "bidirectional"))
      (node (ref "R8") (pin "1") (pinfunction "1_1") (pintype "passive"))
      (node (ref "U1") (pin "40") (pinfunction "PB4(OC2A/PCINT4)_40") (pintype "bidirectional"))
    )
    (net (code "34") (name "PWM2") (class "Default")
      (node (ref "J3") (pin "4") (pinfunction "4_4") (pintype "passive"))
      (node (ref "Q4") (pin "G") (pinfunction "G_G") (pintype "bidirectional"))
      (node (ref "R9") (pin "1") (pinfunction "1_1") (pintype "passive"))
      (node (ref "U1") (pin "41") (pinfunction "PB5(OC1A/PCINT5)_41") (pintype "bidirectional"))
    )
    (net (code "35") (name "PWM3") (class "Default")
      (node (ref "J3") (pin "5") (pinfunction "5_5") (pintype "passive"))
      (node (ref "Q5") (pin "G") (pinfunction "G_G") (pintype "bidirectional"))
      (node (ref "R10") (pin "1") (pinfunction "1_1") (pintype "passive"))
      (node (ref "U1") (pin "42") (pinfunction "PB6(OC1B/PCINT6)_42") (pintype "bidirectional"))
    )
    (net (code "36") (name "PWM4") (class "Default")
      (node (ref "J3") (pin "6") (pinfunction "6_6") (pintype "passive"))
      (node (ref "Q6") (pin "G") (pinfunction "G_G") (pintype "bidirectional"))
      (node (ref "R11") (pin "1") (pinfunction "1_1") (pintype "passive"))
      (node (ref "U1") (pin "43") (pinfunction "PB7(OC0A/OC1C/PCINT7)_43") (pintype "bidirectional"))
    )
    (net (code "37") (name "RESET") (class "Default")
      (node (ref "B3") (pin "1") (pinfunction "1_1") (pintype "passive"))
      (node (ref "B3") (pin "2") (pinfunction "1_2") (pintype "passive"))
      (node (ref "C12") (pin "1") (pinfunction "1_1") (pintype "passive"))
      (node (ref "J2") (pin "5") (pinfunction "5_5") (pintype "passive"))
      (node (ref "R1") (pin "2") (pinfunction "2_2") (pintype "passive"))
      (node (ref "U1") (pin "12") (pinfunction "RSTN_12") (pintype "bidirectional"))
    )
    (net (code "38") (name "RX0") (class "Default")
      (node (ref "J4") (pin "2") (pinfunction "2_2") (pintype "bidirectional"))
      (node (ref "U1") (pin "46") (pinfunction "PE0(RXD0/PCINT8)_46") (pintype "bidirectional"))
    )
    (net (code "39") (name "SCK") (class "Default")
      (node (ref "J2") (pin "3") (pinfunction "3_3") (pintype "passive"))
      (node (ref "U1") (pin "37") (pinfunction "PB1(SCK/PCINT1)_37") (pintype "bidirectional"))
    )
    (net (code "40") (name "SCL") (class "Default")
      (node (ref "J3") (pin "7") (pinfunction "7_7") (pintype "passive"))
      (node (ref "J6") (pin "3") (pinfunction "3_3") (pintype "bidirectional"))
      (node (ref "R5") (pin "2") (pinfunction "2_2") (pintype "passive"))
      (node (ref "U1") (pin "25") (pinfunction "PD0(SCL/INT0)_25") (pintype "bidirectional"))
      (node (ref "U2") (pin "13") (pinfunction "SCL_13") (pintype "bidirectional"))
    )
    (net (code "41") (name "SDA") (class "Default")
      (node (ref "J3") (pin "8") (pinfunction "8_8") (pintype "passive"))
      (node (ref "J6") (pin "4") (pinfunction "4_4") (pintype "bidirectional"))
      (node (ref "R4") (pin "2") (pinfunction "2_2") (pintype "passive"))
      (node (ref "U1") (pin "26") (pinfunction "PD1(SDA/INT1)_26") (pintype "bidirectional"))
      (node (ref "U2") (pin "14") (pinfunction "SDA_14") (pintype "bidirectional"))
    )
    (net (code "42") (name "TX0") (class "Default")
      (node (ref "J4") (pin "1") (pinfunction "1_1") (pintype "bidirectional"))
      (node (ref "U1") (pin "47") (pinfunction "PE1(TXD0)_47") (pintype "bidirectional"))
    )
    (net (code "43") (name "VBAT") (class "Default")
      (node (ref "B2") (pin "2") (pinfunction "P_2") (pintype "bidirectional"))
      (node (ref "C14") (pin "1") (pinfunction "+_1") (pintype "passive"))
      (node (ref "C18") (pin "1") (pinfunction "1_1") (pintype "passive"))
      (node (ref "D5") (pin "1") (pinfunction "C_1") (pintype "passive"))
      (node (ref "D6") (pin "1") (pinfunction "C_1") (pintype "passive"))
      (node (ref "D7") (pin "1") (pinfunction "C_1") (pintype "passive"))
      (node (ref "D8") (pin "1") (pinfunction "C_1") (pintype "passive"))
      (node (ref "J3") (pin "2") (pinfunction "2_2") (pintype "passive"))
      (node (ref "MP1") (pin "1") (pinfunction "V+_1") (pintype "bidirectional"))
      (node (ref "MP2") (pin "1") (pinfunction "V+_1") (pintype "bidirectional"))
      (node (ref "MP3") (pin "1") (pinfunction "V+_1") (pintype "bidirectional"))
      (node (ref "MP4") (pin "1") (pinfunction "V+_1") (pintype "bidirectional"))
      (node (ref "R13") (pin "2") (pinfunction "2_2") (pintype "passive"))
      (node (ref "S2") (pin "B") (pinfunction "ON_B") (pintype "bidirectional"))
      (node (ref "VR1") (pin "1") (pinfunction "IN_1") (pintype "input"))
    )
    (net (code "44") (name "unconnected-(J2-Pad2)") (class "Default")
      (node (ref "J2") (pin "2") (pinfunction "2_2") (pintype "passive"))
    )
    (net (code "45") (name "unconnected-(U1-AREF-Pad62)") (class "Default")
      (node (ref "U1") (pin "62") (pinfunction "AREF_62") (pintype "bidirectional"))
    )
    (net (code "46") (name "unconnected-(U1-PB0(SSN{slash}PCINT0)-Pad36)") (class "Default")
      (node (ref "U1") (pin "36") (pinfunction "PB0(SSN/PCINT0)_36") (pintype "bidirectional"))
    )
    (net (code "47") (name "unconnected-(U1-PD2(RXD1{slash}INT2)-Pad27)") (class "Default")
      (node (ref "U1") (pin "27") (pinfunction "PD2(RXD1/INT2)_27") (pintype "bidirectional"))
    )
    (net (code "48") (name "unconnected-(U1-PD3(TXD1{slash}INT3)-Pad28)") (class "Default")
      (node (ref "U1") (pin "28") (pinfunction "PD3(TXD1/INT3)_28") (pintype "bidirectional"))
    )
    (net (code "49") (name "unconnected-(U1-PD4(ICP1)-Pad29)") (class "Default")
      (node (ref "U1") (pin "29") (pinfunction "PD4(ICP1)_29") (pintype "bidirectional"))
    )
    (net (code "50") (name "unconnected-(U1-PD5(XCK1)-Pad30)") (class "Default")
      (node (ref "U1") (pin "30") (pinfunction "PD5(XCK1)_30") (pintype "bidirectional"))
    )
    (net (code "51") (name "unconnected-(U1-PD6(T1)-Pad31)") (class "Default")
      (node (ref "U1") (pin "31") (pinfunction "PD6(T1)_31") (pintype "bidirectional"))
    )
    (net (code "52") (name "unconnected-(U1-PD7(T0)-Pad32)") (class "Default")
      (node (ref "U1") (pin "32") (pinfunction "PD7(T0)_32") (pintype "bidirectional"))
    )
    (net (code "53") (name "unconnected-(U1-PE2(XCK0{slash}AIN0)-Pad48)") (class "Default")
      (node (ref "U1") (pin "48") (pinfunction "PE2(XCK0/AIN0)_48") (pintype "bidirectional"))
    )
    (net (code "54") (name "unconnected-(U1-PE6(T3{slash}INT6)-Pad52)") (class "Default")
      (node (ref "U1") (pin "52") (pinfunction "PE6(T3/INT6)_52") (pintype "bidirectional"))
    )
    (net (code "55") (name "unconnected-(U1-PE7(ICP3{slash}INT7{slash}CLKO)-Pad53)") (class "Default")
      (node (ref "U1") (pin "53") (pinfunction "PE7(ICP3/INT7/CLKO)_53") (pintype "bidirectional"))
    )
    (net (code "56") (name "unconnected-(U1-PF0(ADC0)-Pad63)") (class "Default")
      (node (ref "U1") (pin "63") (pinfunction "PF0(ADC0)_63") (pintype "bidirectional"))
    )
    (net (code "57") (name "unconnected-(U1-PF2(ADC2{slash}DIG2)-Pad1)") (class "Default")
      (node (ref "U1") (pin "1") (pinfunction "PF2(ADC2/DIG2)_1") (pintype "bidirectional"))
    )
    (net (code "58") (name "unconnected-(U1-PF3(ADC3{slash}DIG4)-Pad2)") (class "Default")
      (node (ref "U1") (pin "2") (pinfunction "PF3(ADC3/DIG4)_2") (pintype "bidirectional"))
    )
    (net (code "59") (name "unconnected-(U1-PF4(ADC4{slash}TCK)-Pad3)") (class "Default")
      (node (ref "U1") (pin "3") (pinfunction "PF4(ADC4/TCK)_3") (pintype "bidirectional"))
    )
    (net (code "60") (name "unconnected-(U1-PF5(ADC5{slash}TMS)-Pad4)") (class "Default")
      (node (ref "U1") (pin "4") (pinfunction "PF5(ADC5/TMS)_4") (pintype "bidirectional"))
    )
    (net (code "61") (name "unconnected-(U1-PF6(ADC6{slash}TDO)-Pad5)") (class "Default")
      (node (ref "U1") (pin "5") (pinfunction "PF6(ADC6/TDO)_5") (pintype "bidirectional"))
    )
    (net (code "62") (name "unconnected-(U1-PF7(ADC7{slash}TDI)-Pad6)") (class "Default")
      (node (ref "U1") (pin "6") (pinfunction "PF7(ADC7/TDI)_6") (pintype "bidirectional"))
    )
    (net (code "63") (name "unconnected-(U1-PG2(AMR)-Pad16)") (class "Default")
      (node (ref "U1") (pin "16") (pinfunction "PG2(AMR)_16") (pintype "bidirectional"))
    )
    (net (code "64") (name "unconnected-(U1-PG3(TOSC2)-Pad17)") (class "Default")
      (node (ref "U1") (pin "17") (pinfunction "PG3(TOSC2)_17") (pintype "bidirectional"))
    )
    (net (code "65") (name "unconnected-(U1-PG4(TOSC1)-Pad18)") (class "Default")
      (node (ref "U1") (pin "18") (pinfunction "PG4(TOSC1)_18") (pintype "bidirectional"))
    )
    (net (code "66") (name "unconnected-(U1-RSTON-Pad13)") (class "Default")
      (node (ref "U1") (pin "13") (pinfunction "RSTON_13") (pintype "bidirectional"))
    )
    (net (code "67") (name "unconnected-(U2-INT1-Pad4)") (class "Default")
      (node (ref "U2") (pin "4") (pinfunction "INT1_4") (pintype "bidirectional"))
    )
    (net (code "68") (name "unconnected-(U2-INT2-Pad9)") (class "Default")
      (node (ref "U2") (pin "9") (pinfunction "INT2_9") (pintype "bidirectional"))
    )
    (net (code "69") (name "unconnected-(U2-OCS_AUX-Pad10)") (class "Default")
      (node (ref "U2") (pin "10") (pinfunction "OCS_AUX_10") (pintype "bidirectional"))
    )
    (net (code "70") (name "unconnected-(U2-SDO_AUX-Pad11)") (class "Default")
      (node (ref "U2") (pin "11") (pinfunction "SDO_AUX_11") (pintype "bidirectional"))
    )
    (net (code "71") (name "unconnected-(VR1-NC{slash}FB-Pad4)") (class "Default")
      (node (ref "VR1") (pin "4") (pinfunction "NC/FB_4") (pintype "passive"))
    )
  )
)
